# SequentialVoltageGenerator.net
KiCad netlist of a schematic drawn in EAGLE
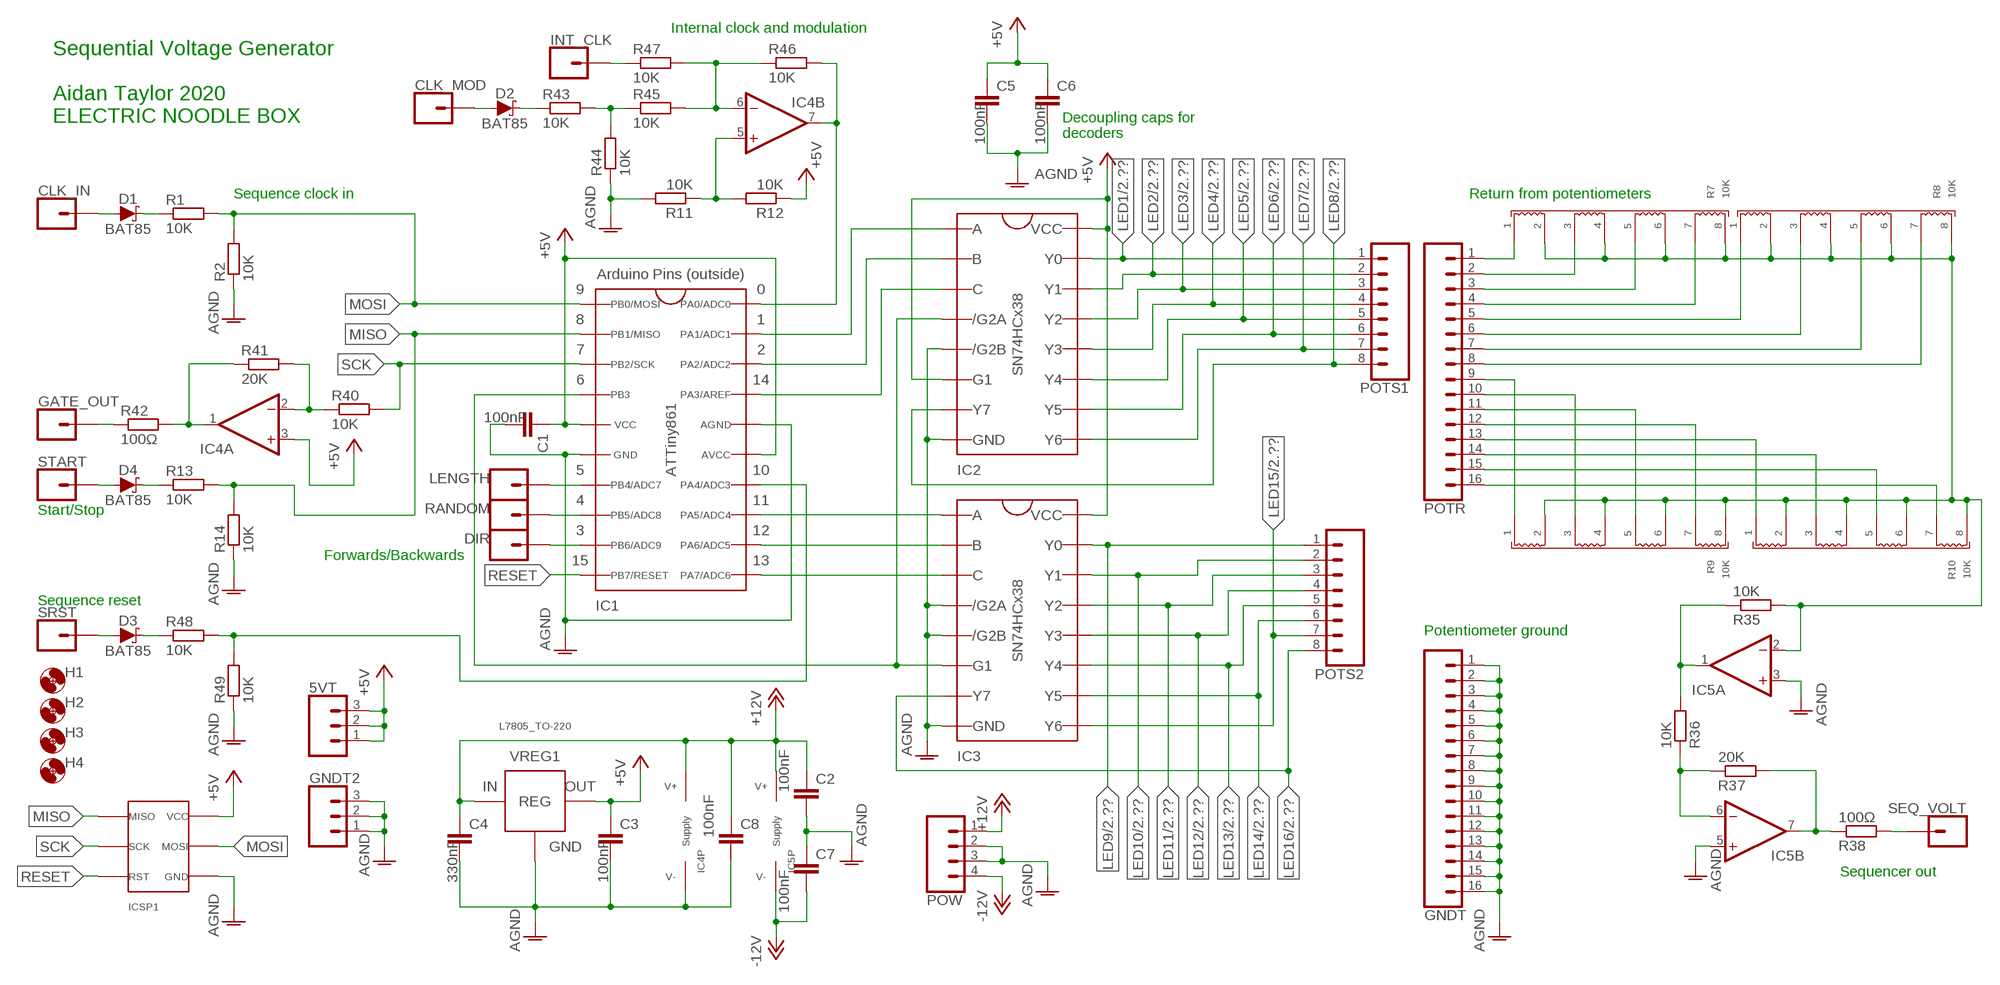
[diagram p0: schematic, sheet 1]
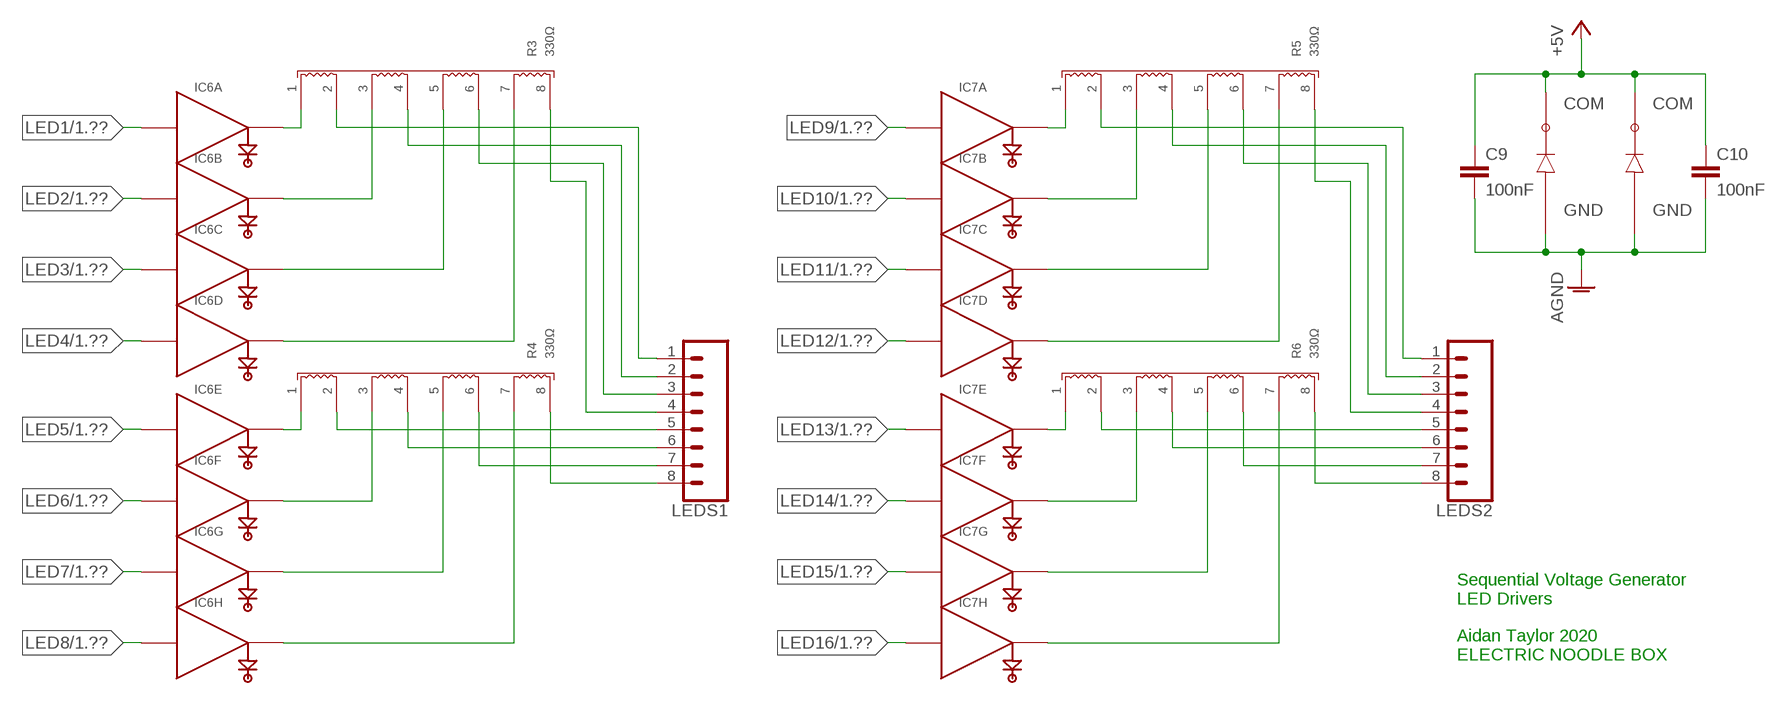
[diagram p1: schematic, sheet 2]

(export (version "E")
  (design (tool "Eeschema 10.0.6"))
  (components
    (comp (ref "C9")
      (value "100nF")
      (footprint "eagle-import:C050-025X075")
      (libsource (lib "eagle-import") (part "C-EU050-025X075"))
    )
    (comp (ref "C10")
      (value "100nF")
      (footprint "eagle-import:C050-025X075")
      (libsource (lib "eagle-import") (part "C-EU050-025X075"))
    )
    (comp (ref "IC6")
      (value "ULN2801_DIP")
      (footprint "eagle-import:DIL18")
      (libsource (lib "eagle-import") (part "ULN2801_DIP"))
    )
    (comp (ref "IC7")
      (value "ULN2801_DIP")
      (footprint "eagle-import:DIL18")
      (libsource (lib "eagle-import") (part "ULN2801_DIP"))
    )
    (comp (ref "LEDS1")
      (value "8XWIREPAD")
      (footprint "eagle-import:1X08")
      (libsource (lib "eagle-import") (part "8XWIREPAD"))
    )
    (comp (ref "LEDS2")
      (value "8XWIREPAD")
      (footprint "eagle-import:1X08")
      (libsource (lib "eagle-import") (part "8XWIREPAD"))
    )
    (comp (ref "R3")
      (value "330Ω")
      (footprint "eagle-import:4_ISO_RES_NET_2.54")
      (libsource (lib "eagle-import") (part "4XISO_RESISTOR_NETWORK_2.54"))
    )
    (comp (ref "R4")
      (value "330Ω")
      (footprint "eagle-import:4_ISO_RES_NET_2.54")
      (libsource (lib "eagle-import") (part "4XISO_RESISTOR_NETWORK_2.54"))
    )
    (comp (ref "R5")
      (value "330Ω")
      (footprint "eagle-import:4_ISO_RES_NET_2.54")
      (libsource (lib "eagle-import") (part "4XISO_RESISTOR_NETWORK_2.54"))
    )
    (comp (ref "R6")
      (value "330Ω")
      (footprint "eagle-import:4_ISO_RES_NET_2.54")
      (libsource (lib "eagle-import") (part "4XISO_RESISTOR_NETWORK_2.54"))
    )
    (comp (ref "5VT")
      (value "3XWIREPAD")
      (footprint "eagle-import:1X03")
      (libsource (lib "eagle-import") (part "3XWIREPAD"))
    )
    (comp (ref "C1")
      (value "100nF")
      (footprint "eagle-import:C050-025X075")
      (libsource (lib "eagle-import") (part "C-EU050-025X075"))
    )
    (comp (ref "C2")
      (value "100nF")
      (footprint "eagle-import:C050-025X075")
      (libsource (lib "eagle-import") (part "C-EU050-025X075"))
    )
    (comp (ref "C3")
      (value "100nF")
      (footprint "eagle-import:C050-025X075")
      (libsource (lib "eagle-import") (part "C-EU050-025X075"))
    )
    (comp (ref "C4")
      (value "330nF")
      (footprint "eagle-import:C050-025X075")
      (libsource (lib "eagle-import") (part "C-EU050-025X075"))
    )
    (comp (ref "C5")
      (value "100nF")
      (footprint "eagle-import:C050-025X075")
      (libsource (lib "eagle-import") (part "C-EU050-025X075"))
    )
    (comp (ref "C6")
      (value "100nF")
      (footprint "eagle-import:C050-025X075")
      (libsource (lib "eagle-import") (part "C-EU050-025X075"))
    )
    (comp (ref "C7")
      (value "100nF")
      (footprint "eagle-import:C050-025X075")
      (libsource (lib "eagle-import") (part "C-EU050-025X075"))
    )
    (comp (ref "C8")
      (value "100nF")
      (footprint "eagle-import:C050-025X075")
      (libsource (lib "eagle-import") (part "C-EU050-025X075"))
    )
    (comp (ref "CLK_IN")
      (value "1XWIREPAD")
      (footprint "eagle-import:1X01")
      (libsource (lib "eagle-import") (part "1XWIREPAD"))
    )
    (comp (ref "CLK_MOD")
      (value "1XWIREPAD")
      (footprint "eagle-import:1X01")
      (libsource (lib "eagle-import") (part "1XWIREPAD"))
    )
    (comp (ref "D1")
      (value "BAT85")
      (footprint "eagle-import:DO35-7")
      (libsource (lib "eagle-import") (part "SCHOTTKY_DO35"))
    )
    (comp (ref "D2")
      (value "BAT85")
      (footprint "eagle-import:DO35-7")
      (libsource (lib "eagle-import") (part "SCHOTTKY_DO35"))
    )
    (comp (ref "D3")
      (value "BAT85")
      (footprint "eagle-import:DO35-7")
      (libsource (lib "eagle-import") (part "SCHOTTKY_DO35"))
    )
    (comp (ref "D4")
      (value "BAT85")
      (footprint "eagle-import:DO35-7")
      (libsource (lib "eagle-import") (part "SCHOTTKY_DO35"))
    )
    (comp (ref "DIR")
      (value "1XWIREPAD")
      (footprint "eagle-import:1X01")
      (libsource (lib "eagle-import") (part "1XWIREPAD"))
    )
    (comp (ref "GATE_OUT")
      (value "1XWIREPAD")
      (footprint "eagle-import:1X01")
      (libsource (lib "eagle-import") (part "1XWIREPAD"))
    )
    (comp (ref "GNDT")
      (value "16XWIREPAD")
      (footprint "eagle-import:1X16")
      (libsource (lib "eagle-import") (part "16XWIREPAD"))
    )
    (comp (ref "GNDT2")
      (value "3XWIREPAD")
      (footprint "eagle-import:1X03")
      (libsource (lib "eagle-import") (part "3XWIREPAD"))
    )
    (comp (ref "H1")
      (value "MOUNT-HOLE3.2")
      (footprint "eagle-import:3,2")
      (libsource (lib "eagle-import") (part "MOUNT-HOLE3.2"))
    )
    (comp (ref "H2")
      (value "MOUNT-HOLE3.2")
      (footprint "eagle-import:3,2")
      (libsource (lib "eagle-import") (part "MOUNT-HOLE3.2"))
    )
    (comp (ref "H3")
      (value "MOUNT-HOLE3.2")
      (footprint "eagle-import:3,2")
      (libsource (lib "eagle-import") (part "MOUNT-HOLE3.2"))
    )
    (comp (ref "H4")
      (value "MOUNT-HOLE3.2")
      (footprint "eagle-import:3,2")
      (libsource (lib "eagle-import") (part "MOUNT-HOLE3.2"))
    )
    (comp (ref "IC1")
      (value "ATTINY861_DIP")
      (footprint "eagle-import:DIL20")
      (libsource (lib "eagle-import") (part "ATTINY861_DIP"))
    )
    (comp (ref "IC2")
      (value "SN74HCX38")
      (footprint "eagle-import:DIL16")
      (libsource (lib "eagle-import") (part "SN74HCX38"))
    )
    (comp (ref "IC3")
      (value "SN74HCX38")
      (footprint "eagle-import:DIL16")
      (libsource (lib "eagle-import") (part "SN74HCX38"))
    )
    (comp (ref "IC4")
      (value "LM358_DIP")
      (footprint "eagle-import:DIL08")
      (libsource (lib "eagle-import") (part "LM358_DIP"))
    )
    (comp (ref "IC5")
      (value "TL0X2_DIP")
      (footprint "eagle-import:DIL08")
      (libsource (lib "eagle-import") (part "TL0X2_DIP"))
    )
    (comp (ref "ICSP1")
      (value "ICSP_2.54")
      (footprint "eagle-import:2X3")
      (libsource (lib "eagle-import") (part "ICSP_2.54"))
    )
    (comp (ref "INT_CLK")
      (value "1XWIREPAD")
      (footprint "eagle-import:1X01")
      (libsource (lib "eagle-import") (part "1XWIREPAD"))
    )
    (comp (ref "LENGTH")
      (value "1XWIREPAD")
      (footprint "eagle-import:1X01")
      (libsource (lib "eagle-import") (part "1XWIREPAD"))
    )
    (comp (ref "POTR")
      (value "16XWIREPAD")
      (footprint "eagle-import:1X16")
      (libsource (lib "eagle-import") (part "16XWIREPAD"))
    )
    (comp (ref "POTS1")
      (value "8XWIREPAD")
      (footprint "eagle-import:1X08")
      (libsource (lib "eagle-import") (part "8XWIREPAD"))
    )
    (comp (ref "POTS2")
      (value "8XWIREPAD")
      (footprint "eagle-import:1X08")
      (libsource (lib "eagle-import") (part "8XWIREPAD"))
    )
    (comp (ref "POW")
      (value "4XMOLEX")
      (footprint "eagle-import:MOLEX-1X4")
      (libsource (lib "eagle-import") (part "4XMOLEX"))
    )
    (comp (ref "R1")
      (value "10K")
      (footprint "eagle-import:0207_10")
      (libsource (lib "eagle-import") (part "R-EU_0207/10"))
    )
    (comp (ref "R2")
      (value "10K")
      (footprint "eagle-import:0207_10")
      (libsource (lib "eagle-import") (part "R-EU_0207/10"))
    )
    (comp (ref "R7")
      (value "10K")
      (footprint "eagle-import:4_ISO_RES_NET_2.54")
      (libsource (lib "eagle-import") (part "4XISO_RESISTOR_NETWORK_2.54"))
    )
    (comp (ref "R8")
      (value "10K")
      (footprint "eagle-import:4_ISO_RES_NET_2.54")
      (libsource (lib "eagle-import") (part "4XISO_RESISTOR_NETWORK_2.54"))
    )
    (comp (ref "R9")
      (value "10K")
      (footprint "eagle-import:4_ISO_RES_NET_2.54")
      (libsource (lib "eagle-import") (part "4XISO_RESISTOR_NETWORK_2.54"))
    )
    (comp (ref "R10")
      (value "10K")
      (footprint "eagle-import:4_ISO_RES_NET_2.54")
      (libsource (lib "eagle-import") (part "4XISO_RESISTOR_NETWORK_2.54"))
    )
    (comp (ref "R11")
      (value "10K")
      (footprint "eagle-import:0207_10")
      (libsource (lib "eagle-import") (part "R-EU_0207/10"))
    )
    (comp (ref "R12")
      (value "10K")
      (footprint "eagle-import:0207_10")
      (libsource (lib "eagle-import") (part "R-EU_0207/10"))
    )
    (comp (ref "R13")
      (value "10K")
      (footprint "eagle-import:0207_10")
      (libsource (lib "eagle-import") (part "R-EU_0207/10"))
    )
    (comp (ref "R14")
      (value "10K")
      (footprint "eagle-import:0207_10")
      (libsource (lib "eagle-import") (part "R-EU_0207/10"))
    )
    (comp (ref "R35")
      (value "10K")
      (footprint "eagle-import:0207_10")
      (libsource (lib "eagle-import") (part "R-EU_0207/10"))
    )
    (comp (ref "R36")
      (value "10K")
      (footprint "eagle-import:0207_10")
      (libsource (lib "eagle-import") (part "R-EU_0207/10"))
    )
    (comp (ref "R37")
      (value "20K")
      (footprint "eagle-import:0207_10")
      (libsource (lib "eagle-import") (part "R-EU_0207/10"))
    )
    (comp (ref "R38")
      (value "100Ω")
      (footprint "eagle-import:0207_10")
      (libsource (lib "eagle-import") (part "R-EU_0207/10"))
    )
    (comp (ref "R40")
      (value "10K")
      (footprint "eagle-import:0207_10")
      (libsource (lib "eagle-import") (part "R-EU_0207/10"))
    )
    (comp (ref "R41")
      (value "20K")
      (footprint "eagle-import:0207_10")
      (libsource (lib "eagle-import") (part "R-EU_0207/10"))
    )
    (comp (ref "R42")
      (value "100Ω")
      (footprint "eagle-import:0207_10")
      (libsource (lib "eagle-import") (part "R-EU_0207/10"))
    )
    (comp (ref "R43")
      (value "10K")
      (footprint "eagle-import:0207_10")
      (libsource (lib "eagle-import") (part "R-EU_0207/10"))
    )
    (comp (ref "R44")
      (value "10K")
      (footprint "eagle-import:0207_10")
      (libsource (lib "eagle-import") (part "R-EU_0207/10"))
    )
    (comp (ref "R45")
      (value "10K")
      (footprint "eagle-import:0207_10")
      (libsource (lib "eagle-import") (part "R-EU_0207/10"))
    )
    (comp (ref "R46")
      (value "10K")
      (footprint "eagle-import:0207_10")
      (libsource (lib "eagle-import") (part "R-EU_0207/10"))
    )
    (comp (ref "R47")
      (value "10K")
      (footprint "eagle-import:0207_10")
      (libsource (lib "eagle-import") (part "R-EU_0207/10"))
    )
    (comp (ref "R48")
      (value "10K")
      (footprint "eagle-import:0207_10")
      (libsource (lib "eagle-import") (part "R-EU_0207/10"))
    )
    (comp (ref "R49")
      (value "10K")
      (footprint "eagle-import:0207_10")
      (libsource (lib "eagle-import") (part "R-EU_0207/10"))
    )
    (comp (ref "RANDOM")
      (value "1XWIREPAD")
      (footprint "eagle-import:1X01")
      (libsource (lib "eagle-import") (part "1XWIREPAD"))
    )
    (comp (ref "SEQ_VOLT")
      (value "1XWIREPAD")
      (footprint "eagle-import:1X01")
      (libsource (lib "eagle-import") (part "1XWIREPAD"))
    )
    (comp (ref "SRST")
      (value "1XWIREPAD")
      (footprint "eagle-import:1X01")
      (libsource (lib "eagle-import") (part "1XWIREPAD"))
    )
    (comp (ref "START")
      (value "1XWIREPAD")
      (footprint "eagle-import:1X01")
      (libsource (lib "eagle-import") (part "1XWIREPAD"))
    )
    (comp (ref "VREG1")
      (value "L7805_TO-220")
      (footprint "eagle-import:TO220H")
      (libsource (lib "eagle-import") (part "L7805_TO-220"))
    )
  )
  (nets
    (net (code "1") (name "+5V") (class "Default")
      (node (ref "5VT") (pin "1") (pinfunction "1_1") (pintype "passive"))
      (node (ref "5VT") (pin "2") (pinfunction "2_2") (pintype "passive"))
      (node (ref "5VT") (pin "3") (pinfunction "3_3") (pintype "passive"))
      (node (ref "C1") (pin "1") (pinfunction "1_1") (pintype "passive"))
      (node (ref "C10") (pin "1") (pinfunction "1_1") (pintype "passive"))
      (node (ref "C3") (pin "1") (pinfunction "1_1") (pintype "passive"))
      (node (ref "C5") (pin "1") (pinfunction "1_1") (pintype "passive"))
      (node (ref "C6") (pin "1") (pinfunction "1_1") (pintype "passive"))
      (node (ref "C9") (pin "1") (pinfunction "1_1") (pintype "passive"))
      (node (ref "IC1") (pin "15") (pinfunction "AVCC_15") (pintype "bidirectional"))
      (node (ref "IC1") (pin "5") (pinfunction "VCC_5") (pintype "power_in"))
      (node (ref "IC2") (pin "16") (pinfunction "16_VCC_16") (pintype "power_in"))
      (node (ref "IC2") (pin "6") (pinfunction "6_G1_6") (pintype "input"))
      (node (ref "IC3") (pin "16") (pinfunction "16_VCC_16") (pintype "power_in"))
      (node (ref "IC4") (pin "3") (pinfunction "+IN_3") (pintype "input"))
      (node (ref "IC6") (pin "10") (pinfunction "COM_10") (pintype "power_in"))
      (node (ref "IC7") (pin "10") (pinfunction "COM_10") (pintype "power_in"))
      (node (ref "ICSP1") (pin "2") (pinfunction "6VCC_2") (pintype "power_in"))
      (node (ref "R12") (pin "1") (pinfunction "1_1") (pintype "passive"))
      (node (ref "VREG1") (pin "3") (pinfunction "VOUT_3") (pintype "output"))
    )
    (net (code "2") (name "+12V") (class "Default")
      (node (ref "C2") (pin "1") (pinfunction "1_1") (pintype "passive"))
      (node (ref "C4") (pin "1") (pinfunction "1_1") (pintype "passive"))
      (node (ref "C8") (pin "1") (pinfunction "1_1") (pintype "passive"))
      (node (ref "IC4") (pin "8") (pinfunction "V+_8") (pintype "bidirectional"))
      (node (ref "IC5") (pin "8") (pinfunction "V+_8") (pintype "bidirectional"))
      (node (ref "POW") (pin "1") (pinfunction "1_1") (pintype "passive"))
      (node (ref "VREG1") (pin "1") (pinfunction "VIN_1") (pintype "input"))
    )
    (net (code "3") (name "-12V") (class "Default")
      (node (ref "C7") (pin "2") (pinfunction "2_2") (pintype "passive"))
      (node (ref "IC5") (pin "4") (pinfunction "V-_4") (pintype "bidirectional"))
      (node (ref "POW") (pin "4") (pinfunction "4_4") (pintype "passive"))
    )
    (net (code "4") (name "AGND") (class "Default")
      (node (ref "C1") (pin "2") (pinfunction "2_2") (pintype "passive"))
      (node (ref "C10") (pin "2") (pinfunction "2_2") (pintype "passive"))
      (node (ref "C2") (pin "2") (pinfunction "2_2") (pintype "passive"))
      (node (ref "C3") (pin "2") (pinfunction "2_2") (pintype "passive"))
      (node (ref "C4") (pin "2") (pinfunction "2_2") (pintype "passive"))
      (node (ref "C5") (pin "2") (pinfunction "2_2") (pintype "passive"))
      (node (ref "C6") (pin "2") (pinfunction "2_2") (pintype "passive"))
      (node (ref "C7") (pin "1") (pinfunction "1_1") (pintype "passive"))
      (node (ref "C8") (pin "2") (pinfunction "2_2") (pintype "passive"))
      (node (ref "C9") (pin "2") (pinfunction "2_2") (pintype "passive"))
      (node (ref "GNDT") (pin "1") (pinfunction "1_1") (pintype "passive"))
      (node (ref "GNDT") (pin "10") (pinfunction "10_10") (pintype "passive"))
      (node (ref "GNDT") (pin "11") (pinfunction "11_11") (pintype "passive"))
      (node (ref "GNDT") (pin "12") (pinfunction "12_12") (pintype "passive"))
      (node (ref "GNDT") (pin "13") (pinfunction "13_13") (pintype "passive"))
      (node (ref "GNDT") (pin "14") (pinfunction "14_14") (pintype "passive"))
      (node (ref "GNDT") (pin "15") (pinfunction "15_15") (pintype "passive"))
      (node (ref "GNDT") (pin "16") (pinfunction "16_16") (pintype "passive"))
      (node (ref "GNDT") (pin "2") (pinfunction "2_2") (pintype "passive"))
      (node (ref "GNDT") (pin "3") (pinfunction "3_3") (pintype "passive"))
      (node (ref "GNDT") (pin "4") (pinfunction "4_4") (pintype "passive"))
      (node (ref "GNDT") (pin "5") (pinfunction "5_5") (pintype "passive"))
      (node (ref "GNDT") (pin "6") (pinfunction "6_6") (pintype "passive"))
      (node (ref "GNDT") (pin "7") (pinfunction "7_7") (pintype "passive"))
      (node (ref "GNDT") (pin "8") (pinfunction "8_8") (pintype "passive"))
      (node (ref "GNDT") (pin "9") (pinfunction "9_9") (pintype "passive"))
      (node (ref "GNDT2") (pin "1") (pinfunction "1_1") (pintype "passive"))
      (node (ref "GNDT2") (pin "2") (pinfunction "2_2") (pintype "passive"))
      (node (ref "GNDT2") (pin "3") (pinfunction "3_3") (pintype "passive"))
      (node (ref "IC1") (pin "16") (pinfunction "AGND_16") (pintype "bidirectional"))
      (node (ref "IC1") (pin "6") (pinfunction "GND_6") (pintype "power_in"))
      (node (ref "IC2") (pin "5") (pinfunction "5_/G2B_5") (pintype "input"))
      (node (ref "IC2") (pin "8") (pinfunction "8_GND_8") (pintype "power_in"))
      (node (ref "IC3") (pin "4") (pinfunction "4_/G2A_4") (pintype "input"))
      (node (ref "IC3") (pin "5") (pinfunction "5_/G2B_5") (pintype "input"))
      (node (ref "IC3") (pin "8") (pinfunction "8_GND_8") (pintype "power_in"))
      (node (ref "IC4") (pin "4") (pinfunction "V-_4") (pintype "bidirectional"))
      (node (ref "IC5") (pin "3") (pinfunction "+IN_3") (pintype "input"))
      (node (ref "IC5") (pin "5") (pinfunction "+IN_5") (pintype "input"))
      (node (ref "IC6") (pin "9") (pinfunction "GND_9") (pintype "power_in"))
      (node (ref "IC7") (pin "9") (pinfunction "GND_9") (pintype "power_in"))
      (node (ref "ICSP1") (pin "6") (pinfunction "4GND_6") (pintype "power_in"))
      (node (ref "POW") (pin "2") (pinfunction "2_2") (pintype "passive"))
      (node (ref "POW") (pin "3") (pinfunction "3_3") (pintype "passive"))
      (node (ref "R11") (pin "2") (pinfunction "2_2") (pintype "passive"))
      (node (ref "R14") (pin "1") (pinfunction "1_1") (pintype "passive"))
      (node (ref "R2") (pin "1") (pinfunction "1_1") (pintype "passive"))
      (node (ref "R44") (pin "1") (pinfunction "1_1") (pintype "passive"))
      (node (ref "R49") (pin "1") (pinfunction "1_1") (pintype "passive"))
      (node (ref "VREG1") (pin "2") (pinfunction "GND_2") (pintype "power_in"))
    )
    (net (code "5") (name "LED1") (class "Default")
      (node (ref "IC2") (pin "15") (pinfunction "15_Y0_15") (pintype "output"))
      (node (ref "IC6") (pin "1") (pinfunction "IN_1") (pintype "input"))
      (node (ref "POTS1") (pin "1") (pinfunction "1_1") (pintype "passive"))
    )
    (net (code "6") (name "LED2") (class "Default")
      (node (ref "IC2") (pin "14") (pinfunction "14_Y1_14") (pintype "output"))
      (node (ref "IC6") (pin "2") (pinfunction "IN_2") (pintype "input"))
      (node (ref "POTS1") (pin "2") (pinfunction "2_2") (pintype "passive"))
    )
    (net (code "7") (name "LED3") (class "Default")
      (node (ref "IC2") (pin "13") (pinfunction "13_Y2_13") (pintype "output"))
      (node (ref "IC6") (pin "3") (pinfunction "IN_3") (pintype "input"))
      (node (ref "POTS1") (pin "3") (pinfunction "3_3") (pintype "passive"))
    )
    (net (code "8") (name "LED4") (class "Default")
      (node (ref "IC2") (pin "12") (pinfunction "12_Y3_12") (pintype "output"))
      (node (ref "IC6") (pin "4") (pinfunction "IN_4") (pintype "input"))
      (node (ref "POTS1") (pin "4") (pinfunction "4_4") (pintype "passive"))
    )
    (net (code "9") (name "LED5") (class "Default")
      (node (ref "IC2") (pin "11") (pinfunction "11_Y4_11") (pintype "output"))
      (node (ref "IC6") (pin "5") (pinfunction "IN_5") (pintype "input"))
      (node (ref "POTS1") (pin "5") (pinfunction "5_5") (pintype "passive"))
    )
    (net (code "10") (name "LED6") (class "Default")
      (node (ref "IC2") (pin "10") (pinfunction "10_Y5_10") (pintype "output"))
      (node (ref "IC6") (pin "6") (pinfunction "IN_6") (pintype "input"))
      (node (ref "POTS1") (pin "6") (pinfunction "6_6") (pintype "passive"))
    )
    (net (code "11") (name "LED7") (class "Default")
      (node (ref "IC2") (pin "9") (pinfunction "9_Y6_9") (pintype "output"))
      (node (ref "IC6") (pin "7") (pinfunction "IN_7") (pintype "input"))
      (node (ref "POTS1") (pin "7") (pinfunction "7_7") (pintype "passive"))
    )
    (net (code "12") (name "LED8") (class "Default")
      (node (ref "IC2") (pin "7") (pinfunction "7_Y7_7") (pintype "output"))
      (node (ref "IC6") (pin "8") (pinfunction "IN_8") (pintype "input"))
      (node (ref "POTS1") (pin "8") (pinfunction "8_8") (pintype "passive"))
    )
    (net (code "13") (name "LED9") (class "Default")
      (node (ref "IC3") (pin "15") (pinfunction "15_Y0_15") (pintype "output"))
      (node (ref "IC7") (pin "1") (pinfunction "IN_1") (pintype "input"))
      (node (ref "POTS2") (pin "1") (pinfunction "1_1") (pintype "passive"))
    )
    (net (code "14") (name "LED10") (class "Default")
      (node (ref "IC3") (pin "14") (pinfunction "14_Y1_14") (pintype "output"))
      (node (ref "IC7") (pin "2") (pinfunction "IN_2") (pintype "input"))
      (node (ref "POTS2") (pin "2") (pinfunction "2_2") (pintype "passive"))
    )
    (net (code "15") (name "LED11") (class "Default")
      (node (ref "IC3") (pin "13") (pinfunction "13_Y2_13") (pintype "output"))
      (node (ref "IC7") (pin "3") (pinfunction "IN_3") (pintype "input"))
      (node (ref "POTS2") (pin "3") (pinfunction "3_3") (pintype "passive"))
    )
    (net (code "16") (name "LED12") (class "Default")
      (node (ref "IC3") (pin "12") (pinfunction "12_Y3_12") (pintype "output"))
      (node (ref "IC7") (pin "4") (pinfunction "IN_4") (pintype "input"))
      (node (ref "POTS2") (pin "4") (pinfunction "4_4") (pintype "passive"))
    )
    (net (code "17") (name "LED13") (class "Default")
      (node (ref "IC3") (pin "11") (pinfunction "11_Y4_11") (pintype "output"))
      (node (ref "IC7") (pin "5") (pinfunction "IN_5") (pintype "input"))
      (node (ref "POTS2") (pin "5") (pinfunction "5_5") (pintype "passive"))
    )
    (net (code "18") (name "LED14") (class "Default")
      (node (ref "IC3") (pin "10") (pinfunction "10_Y5_10") (pintype "output"))
      (node (ref "IC7") (pin "6") (pinfunction "IN_6") (pintype "input"))
      (node (ref "POTS2") (pin "6") (pinfunction "6_6") (pintype "passive"))
    )
    (net (code "19") (name "LED15") (class "Default")
      (node (ref "IC3") (pin "9") (pinfunction "9_Y6_9") (pintype "output"))
      (node (ref "IC7") (pin "7") (pinfunction "IN_7") (pintype "input"))
      (node (ref "POTS2") (pin "7") (pinfunction "7_7") (pintype "passive"))
    )
    (net (code "20") (name "LED16") (class "Default")
      (node (ref "IC3") (pin "7") (pinfunction "7_Y7_7") (pintype "output"))
      (node (ref "IC7") (pin "8") (pinfunction "IN_8") (pintype "input"))
      (node (ref "POTS2") (pin "8") (pinfunction "8_8") (pintype "passive"))
    )
    (net (code "21") (name "MISO") (class "Default")
      (node (ref "IC1") (pin "2") (pinfunction "2_PB1_2") (pintype "bidirectional"))
      (node (ref "ICSP1") (pin "1") (pinfunction "1MISO_1") (pintype "bidirectional"))
      (node (ref "R13") (pin "2") (pinfunction "2_2") (pintype "passive"))
      (node (ref "R14") (pin "2") (pinfunction "2_2") (pintype "passive"))
    )
    (net (code "22") (name "MOSI") (class "Default")
      (node (ref "IC1") (pin "1") (pinfunction "1_PB0_1") (pintype "bidirectional"))
      (node (ref "ICSP1") (pin "4") (pinfunction "5MOSI_4") (pintype "bidirectional"))
      (node (ref "R1") (pin "2") (pinfunction "2_2") (pintype "passive"))
      (node (ref "R2") (pin "2") (pinfunction "2_2") (pintype "passive"))
    )
    (net (code "23") (name "Net-(CLK_IN-Pad1)") (class "Default")
      (node (ref "CLK_IN") (pin "1") (pinfunction "1_1") (pintype "passive"))
      (node (ref "D1") (pin "A") (pinfunction "A_A") (pintype "passive"))
    )
    (net (code "24") (name "Net-(CLK_MOD-Pad1)") (class "Default")
      (node (ref "CLK_MOD") (pin "1") (pinfunction "1_1") (pintype "passive"))
      (node (ref "D2") (pin "A") (pinfunction "A_A") (pintype "passive"))
    )
    (net (code "25") (name "Net-(D1-PadC)") (class "Default")
      (node (ref "D1") (pin "C") (pinfunction "C_C") (pintype "passive"))
      (node (ref "R1") (pin "1") (pinfunction "1_1") (pintype "passive"))
    )
    (net (code "26") (name "Net-(D2-PadC)") (class "Default")
      (node (ref "D2") (pin "C") (pinfunction "C_C") (pintype "passive"))
      (node (ref "R43") (pin "1") (pinfunction "1_1") (pintype "passive"))
    )
    (net (code "27") (name "Net-(D3-PadA)") (class "Default")
      (node (ref "D3") (pin "A") (pinfunction "A_A") (pintype "passive"))
      (node (ref "SRST") (pin "1") (pinfunction "1_1") (pintype "passive"))
    )
    (net (code "28") (name "Net-(D3-PadC)") (class "Default")
      (node (ref "D3") (pin "C") (pinfunction "C_C") (pintype "passive"))
      (node (ref "R48") (pin "1") (pinfunction "1_1") (pintype "passive"))
    )
    (net (code "29") (name "Net-(D4-PadA)") (class "Default")
      (node (ref "D4") (pin "A") (pinfunction "A_A") (pintype "passive"))
      (node (ref "START") (pin "1") (pinfunction "1_1") (pintype "passive"))
    )
    (net (code "30") (name "Net-(D4-PadC)") (class "Default")
      (node (ref "D4") (pin "C") (pinfunction "C_C") (pintype "passive"))
      (node (ref "R13") (pin "1") (pinfunction "1_1") (pintype "passive"))
    )
    (net (code "31") (name "Net-(GATE_OUT-Pad1)") (class "Default")
      (node (ref "GATE_OUT") (pin "1") (pinfunction "1_1") (pintype "passive"))
      (node (ref "R42") (pin "1") (pinfunction "1_1") (pintype "passive"))
    )
    (net (code "32") (name "Net-(IC1-4_PB3)") (class "Default")
      (node (ref "IC1") (pin "4") (pinfunction "4_PB3_4") (pintype "bidirectional"))
      (node (ref "IC2") (pin "4") (pinfunction "4_/G2A_4") (pintype "input"))
      (node (ref "IC3") (pin "6") (pinfunction "6_G1_6") (pintype "input"))
    )
    (net (code "33") (name "Net-(IC1-7_PB4)") (class "Default")
      (node (ref "IC1") (pin "7") (pinfunction "7_PB4_7") (pintype "bidirectional"))
      (node (ref "LENGTH") (pin "1") (pinfunction "1_1") (pintype "passive"))
    )
    (net (code "34") (name "Net-(IC1-8_PB5)") (class "Default")
      (node (ref "IC1") (pin "8") (pinfunction "8_PB5_8") (pintype "bidirectional"))
      (node (ref "RANDOM") (pin "1") (pinfunction "1_1") (pintype "passive"))
    )
    (net (code "35") (name "Net-(IC1-9_PB6)") (class "Default")
      (node (ref "DIR") (pin "1") (pinfunction "1_1") (pintype "passive"))
      (node (ref "IC1") (pin "9") (pinfunction "9_PB6_9") (pintype "bidirectional"))
    )
    (net (code "36") (name "Net-(IC1-11_PA7)") (class "Default")
      (node (ref "IC1") (pin "11") (pinfunction "11_PA7_11") (pintype "bidirectional"))
      (node (ref "IC3") (pin "3") (pinfunction "3_C_3") (pintype "input"))
    )
    (net (code "37") (name "Net-(IC1-12_PA6)") (class "Default")
      (node (ref "IC1") (pin "12") (pinfunction "12_PA6_12") (pintype "bidirectional"))
      (node (ref "IC3") (pin "2") (pinfunction "2_B_2") (pintype "input"))
    )
    (net (code "38") (name "Net-(IC1-13_PA5)") (class "Default")
      (node (ref "IC1") (pin "13") (pinfunction "13_PA5_13") (pintype "bidirectional"))
      (node (ref "IC3") (pin "1") (pinfunction "1_A_1") (pintype "input"))
    )
    (net (code "39") (name "Net-(IC1-14_PA4)") (class "Default")
      (node (ref "IC1") (pin "14") (pinfunction "14_PA4_14") (pintype "bidirectional"))
      (node (ref "R48") (pin "2") (pinfunction "2_2") (pintype "passive"))
      (node (ref "R49") (pin "2") (pinfunction "2_2") (pintype "passive"))
    )
    (net (code "40") (name "Net-(IC1-17_PA3)") (class "Default")
      (node (ref "IC1") (pin "17") (pinfunction "17_PA3_17") (pintype "bidirectional"))
      (node (ref "IC2") (pin "3") (pinfunction "3_C_3") (pintype "input"))
    )
    (net (code "41") (name "Net-(IC1-18_PA2)") (class "Default")
      (node (ref "IC1") (pin "18") (pinfunction "18_PA2_18") (pintype "bidirectional"))
      (node (ref "IC2") (pin "2") (pinfunction "2_B_2") (pintype "input"))
    )
    (net (code "42") (name "Net-(IC1-19_PA1)") (class "Default")
      (node (ref "IC1") (pin "19") (pinfunction "19_PA1_19") (pintype "bidirectional"))
      (node (ref "IC2") (pin "1") (pinfunction "1_A_1") (pintype "input"))
    )
    (net (code "43") (name "Net-(IC1-20_PA0)") (class "Default")
      (node (ref "IC1") (pin "20") (pinfunction "20_PA0_20") (pintype "bidirectional"))
      (node (ref "IC4") (pin "7") (pinfunction "OUT_7") (pintype "output"))
      (node (ref "R46") (pin "2") (pinfunction "2_2") (pintype "passive"))
    )
    (net (code "44") (name "Net-(IC4A--IN)") (class "Default")
      (node (ref "IC4") (pin "2") (pinfunction "-IN_2") (pintype "input"))
      (node (ref "R40") (pin "1") (pinfunction "1_1") (pintype "passive"))
      (node (ref "R41") (pin "2") (pinfunction "2_2") (pintype "passive"))
    )
    (net (code "45") (name "Net-(IC4A-OUT)") (class "Default")
      (node (ref "IC4") (pin "1") (pinfunction "OUT_1") (pintype "output"))
      (node (ref "R41") (pin "1") (pinfunction "1_1") (pintype "passive"))
      (node (ref "R42") (pin "2") (pinfunction "2_2") (pintype "passive"))
    )
    (net (code "46") (name "Net-(IC4B-+IN)") (class "Default")
      (node (ref "IC4") (pin "5") (pinfunction "+IN_5") (pintype "input"))
      (node (ref "R11") (pin "1") (pinfunction "1_1") (pintype "passive"))
      (node (ref "R12") (pin "2") (pinfunction "2_2") (pintype "passive"))
    )
    (net (code "47") (name "Net-(IC4B--IN)") (class "Default")
      (node (ref "IC4") (pin "6") (pinfunction "-IN_6") (pintype "input"))
      (node (ref "R45") (pin "2") (pinfunction "2_2") (pintype "passive"))
      (node (ref "R46") (pin "1") (pinfunction "1_1") (pintype "passive"))
      (node (ref "R47") (pin "2") (pinfunction "2_2") (pintype "passive"))
    )
    (net (code "48") (name "Net-(IC5A--IN)") (class "Default")
      (node (ref "IC5") (pin "2") (pinfunction "-IN_2") (pintype "input"))
      (node (ref "R10") (pin "P$2") (pinfunction "P$2_P$2") (pintype "bidirectional"))
      (node (ref "R10") (pin "P$4") (pinfunction "P$4_P$4") (pintype "bidirectional"))
      (node (ref "R10") (pin "P$6") (pinfunction "P$6_P$6") (pintype "bidirectional"))
      (node (ref "R10") (pin "P$8") (pinfunction "P$8_P$8") (pintype "bidirectional"))
      (node (ref "R35") (pin "2") (pinfunction "2_2") (pintype "passive"))
      (node (ref "R7") (pin "P$2") (pinfunction "P$2_P$2") (pintype "bidirectional"))
      (node (ref "R7") (pin "P$4") (pinfunction "P$4_P$4") (pintype "bidirectional"))
      (node (ref "R7") (pin "P$6") (pinfunction "P$6_P$6") (pintype "bidirectional"))
      (node (ref "R7") (pin "P$8") (pinfunction "P$8_P$8") (pintype "bidirectional"))
      (node (ref "R8") (pin "P$2") (pinfunction "P$2_P$2") (pintype "bidirectional"))
      (node (ref "R8") (pin "P$4") (pinfunction "P$4_P$4") (pintype "bidirectional"))
      (node (ref "R8") (pin "P$6") (pinfunction "P$6_P$6") (pintype "bidirectional"))
      (node (ref "R8") (pin "P$8") (pinfunction "P$8_P$8") (pintype "bidirectional"))
      (node (ref "R9") (pin "P$2") (pinfunction "P$2_P$2") (pintype "bidirectional"))
      (node (ref "R9") (pin "P$4") (pinfunction "P$4_P$4") (pintype "bidirectional"))
      (node (ref "R9") (pin "P$6") (pinfunction "P$6_P$6") (pintype "bidirectional"))
      (node (ref "R9") (pin "P$8") (pinfunction "P$8_P$8") (pintype "bidirectional"))
    )
    (net (code "49") (name "Net-(IC5A-OUT)") (class "Default")
      (node (ref "IC5") (pin "1") (pinfunction "OUT_1") (pintype "output"))
      (node (ref "R35") (pin "1") (pinfunction "1_1") (pintype "passive"))
      (node (ref "R36") (pin "2") (pinfunction "2_2") (pintype "passive"))
    )
    (net (code "50") (name "Net-(IC5B--IN)") (class "Default")
      (node (ref "IC5") (pin "6") (pinfunction "-IN_6") (pintype "input"))
      (node (ref "R36") (pin "1") (pinfunction "1_1") (pintype "passive"))
      (node (ref "R37") (pin "1") (pinfunction "1_1") (pintype "passive"))
    )
    (net (code "51") (name "Net-(IC5B-OUT)") (class "Default")
      (node (ref "IC5") (pin "7") (pinfunction "OUT_7") (pintype "output"))
      (node (ref "R37") (pin "2") (pinfunction "2_2") (pintype "passive"))
      (node (ref "R38") (pin "1") (pinfunction "1_1") (pintype "passive"))
    )
    (net (code "52") (name "Net-(IC6A-P$2)") (class "Default")
      (node (ref "IC6") (pin "18") (pinfunction "P$2_18") (pintype "output"))
      (node (ref "R3") (pin "P$1") (pinfunction "P$1_P$1") (pintype "bidirectional"))
    )
    (net (code "53") (name "Net-(IC6B-P$2)") (class "Default")
      (node (ref "IC6") (pin "17") (pinfunction "P$2_17") (pintype "output"))
      (node (ref "R3") (pin "P$3") (pinfunction "P$3_P$3") (pintype "bidirectional"))
    )
    (net (code "54") (name "Net-(IC6C-P$2)") (class "Default")
      (node (ref "IC6") (pin "16") (pinfunction "P$2_16") (pintype "output"))
      (node (ref "R3") (pin "P$5") (pinfunction "P$5_P$5") (pintype "bidirectional"))
    )
    (net (code "55") (name "Net-(IC6D-P$2)") (class "Default")
      (node (ref "IC6") (pin "15") (pinfunction "P$2_15") (pintype "output"))
      (node (ref "R3") (pin "P$7") (pinfunction "P$7_P$7") (pintype "bidirectional"))
    )
    (net (code "56") (name "Net-(IC6E-P$2)") (class "Default")
      (node (ref "IC6") (pin "14") (pinfunction "P$2_14") (pintype "output"))
      (node (ref "R4") (pin "P$1") (pinfunction "P$1_P$1") (pintype "bidirectional"))
    )
    (net (code "57") (name "Net-(IC6F-P$2)") (class "Default")
      (node (ref "IC6") (pin "13") (pinfunction "P$2_13") (pintype "output"))
      (node (ref "R4") (pin "P$3") (pinfunction "P$3_P$3") (pintype "bidirectional"))
    )
    (net (code "58") (name "Net-(IC6G-P$2)") (class "Default")
      (node (ref "IC6") (pin "12") (pinfunction "P$2_12") (pintype "output"))
      (node (ref "R4") (pin "P$5") (pinfunction "P$5_P$5") (pintype "bidirectional"))
    )
    (net (code "59") (name "Net-(IC6I-P$2)") (class "Default")
      (node (ref "IC6") (pin "11") (pinfunction "P$2_11") (pintype "output"))
      (node (ref "R4") (pin "P$7") (pinfunction "P$7_P$7") (pintype "bidirectional"))
    )
    (net (code "60") (name "Net-(IC7A-P$2)") (class "Default")
      (node (ref "IC7") (pin "18") (pinfunction "P$2_18") (pintype "output"))
      (node (ref "R5") (pin "P$1") (pinfunction "P$1_P$1") (pintype "bidirectional"))
    )
    (net (code "61") (name "Net-(IC7B-P$2)") (class "Default")
      (node (ref "IC7") (pin "17") (pinfunction "P$2_17") (pintype "output"))
      (node (ref "R5") (pin "P$3") (pinfunction "P$3_P$3") (pintype "bidirectional"))
    )
    (net (code "62") (name "Net-(IC7C-P$2)") (class "Default")
      (node (ref "IC7") (pin "16") (pinfunction "P$2_16") (pintype "output"))
      (node (ref "R5") (pin "P$5") (pinfunction "P$5_P$5") (pintype "bidirectional"))
    )
    (net (code "63") (name "Net-(IC7D-P$2)") (class "Default")
      (node (ref "IC7") (pin "15") (pinfunction "P$2_15") (pintype "output"))
      (node (ref "R5") (pin "P$7") (pinfunction "P$7_P$7") (pintype "bidirectional"))
    )
    (net (code "64") (name "Net-(IC7E-P$2)") (class "Default")
      (node (ref "IC7") (pin "14") (pinfunction "P$2_14") (pintype "output"))
      (node (ref "R6") (pin "P$1") (pinfunction "P$1_P$1") (pintype "bidirectional"))
    )
    (net (code "65") (name "Net-(IC7F-P$2)") (class "Default")
      (node (ref "IC7") (pin "13") (pinfunction "P$2_13") (pintype "output"))
      (node (ref "R6") (pin "P$3") (pinfunction "P$3_P$3") (pintype "bidirectional"))
    )
    (net (code "66") (name "Net-(IC7G-P$2)") (class "Default")
      (node (ref "IC7") (pin "12") (pinfunction "P$2_12") (pintype "output"))
      (node (ref "R6") (pin "P$5") (pinfunction "P$5_P$5") (pintype "bidirectional"))
    )
    (net (code "67") (name "Net-(IC7I-P$2)") (class "Default")
      (node (ref "IC7") (pin "11") (pinfunction "P$2_11") (pintype "output"))
      (node (ref "R6") (pin "P$7") (pinfunction "P$7_P$7") (pintype "bidirectional"))
    )
    (net (code "68") (name "Net-(INT_CLK-Pad1)") (class "Default")
      (node (ref "INT_CLK") (pin "1") (pinfunction "1_1") (pintype "passive"))
      (node (ref "R47") (pin "1") (pinfunction "1_1") (pintype "passive"))
    )
    (net (code "69") (name "Net-(LEDS1-Pad1)") (class "Default")
      (node (ref "LEDS1") (pin "1") (pinfunction "1_1") (pintype "passive"))
      (node (ref "R3") (pin "P$2") (pinfunction "P$2_P$2") (pintype "bidirectional"))
    )
    (net (code "70") (name "Net-(LEDS1-Pad2)") (class "Default")
      (node (ref "LEDS1") (pin "2") (pinfunction "2_2") (pintype "passive"))
      (node (ref "R3") (pin "P$4") (pinfunction "P$4_P$4") (pintype "bidirectional"))
    )
    (net (code "71") (name "Net-(LEDS1-Pad3)") (class "Default")
      (node (ref "LEDS1") (pin "3") (pinfunction "3_3") (pintype "passive"))
      (node (ref "R3") (pin "P$6") (pinfunction "P$6_P$6") (pintype "bidirectional"))
    )
    (net (code "72") (name "Net-(LEDS1-Pad4)") (class "Default")
      (node (ref "LEDS1") (pin "4") (pinfunction "4_4") (pintype "passive"))
      (node (ref "R3") (pin "P$8") (pinfunction "P$8_P$8") (pintype "bidirectional"))
    )
    (net (code "73") (name "Net-(LEDS1-Pad5)") (class "Default")
      (node (ref "LEDS1") (pin "5") (pinfunction "5_5") (pintype "passive"))
      (node (ref "R4") (pin "P$2") (pinfunction "P$2_P$2") (pintype "bidirectional"))
    )
    (net (code "74") (name "Net-(LEDS1-Pad6)") (class "Default")
      (node (ref "LEDS1") (pin "6") (pinfunction "6_6") (pintype "passive"))
      (node (ref "R4") (pin "P$4") (pinfunction "P$4_P$4") (pintype "bidirectional"))
    )
    (net (code "75") (name "Net-(LEDS1-Pad7)") (class "Default")
      (node (ref "LEDS1") (pin "7") (pinfunction "7_7") (pintype "passive"))
      (node (ref "R4") (pin "P$6") (pinfunction "P$6_P$6") (pintype "bidirectional"))
    )
    (net (code "76") (name "Net-(LEDS1-Pad8)") (class "Default")
      (node (ref "LEDS1") (pin "8") (pinfunction "8_8") (pintype "passive"))
      (node (ref "R4") (pin "P$8") (pinfunction "P$8_P$8") (pintype "bidirectional"))
    )
    (net (code "77") (name "Net-(LEDS2-Pad1)") (class "Default")
      (node (ref "LEDS2") (pin "1") (pinfunction "1_1") (pintype "passive"))
      (node (ref "R5") (pin "P$2") (pinfunction "P$2_P$2") (pintype "bidirectional"))
    )
    (net (code "78") (name "Net-(LEDS2-Pad2)") (class "Default")
      (node (ref "LEDS2") (pin "2") (pinfunction "2_2") (pintype "passive"))
      (node (ref "R5") (pin "P$4") (pinfunction "P$4_P$4") (pintype "bidirectional"))
    )
    (net (code "79") (name "Net-(LEDS2-Pad3)") (class "Default")
      (node (ref "LEDS2") (pin "3") (pinfunction "3_3") (pintype "passive"))
      (node (ref "R5") (pin "P$6") (pinfunction "P$6_P$6") (pintype "bidirectional"))
    )
    (net (code "80") (name "Net-(LEDS2-Pad4)") (class "Default")
      (node (ref "LEDS2") (pin "4") (pinfunction "4_4") (pintype "passive"))
      (node (ref "R5") (pin "P$8") (pinfunction "P$8_P$8") (pintype "bidirectional"))
    )
    (net (code "81") (name "Net-(LEDS2-Pad5)") (class "Default")
      (node (ref "LEDS2") (pin "5") (pinfunction "5_5") (pintype "passive"))
      (node (ref "R6") (pin "P$2") (pinfunction "P$2_P$2") (pintype "bidirectional"))
    )
    (net (code "82") (name "Net-(LEDS2-Pad6)") (class "Default")
      (node (ref "LEDS2") (pin "6") (pinfunction "6_6") (pintype "passive"))
      (node (ref "R6") (pin "P$4") (pinfunction "P$4_P$4") (pintype "bidirectional"))
    )
    (net (code "83") (name "Net-(LEDS2-Pad7)") (class "Default")
      (node (ref "LEDS2") (pin "7") (pinfunction "7_7") (pintype "passive"))
      (node (ref "R6") (pin "P$6") (pinfunction "P$6_P$6") (pintype "bidirectional"))
    )
    (net (code "84") (name "Net-(LEDS2-Pad8)") (class "Default")
      (node (ref "LEDS2") (pin "8") (pinfunction "8_8") (pintype "passive"))
      (node (ref "R6") (pin "P$8") (pinfunction "P$8_P$8") (pintype "bidirectional"))
    )
    (net (code "85") (name "Net-(POTR-Pad1)") (class "Default")
      (node (ref "POTR") (pin "1") (pinfunction "1_1") (pintype "passive"))
      (node (ref "R7") (pin "P$1") (pinfunction "P$1_P$1") (pintype "bidirectional"))
    )
    (net (code "86") (name "Net-(POTR-Pad2)") (class "Default")
      (node (ref "POTR") (pin "2") (pinfunction "2_2") (pintype "passive"))
      (node (ref "R7") (pin "P$3") (pinfunction "P$3_P$3") (pintype "bidirectional"))
    )
    (net (code "87") (name "Net-(POTR-Pad3)") (class "Default")
      (node (ref "POTR") (pin "3") (pinfunction "3_3") (pintype "passive"))
      (node (ref "R7") (pin "P$5") (pinfunction "P$5_P$5") (pintype "bidirectional"))
    )
    (net (code "88") (name "Net-(POTR-Pad4)") (class "Default")
      (node (ref "POTR") (pin "4") (pinfunction "4_4") (pintype "passive"))
      (node (ref "R7") (pin "P$7") (pinfunction "P$7_P$7") (pintype "bidirectional"))
    )
    (net (code "89") (name "Net-(POTR-Pad5)") (class "Default")
      (node (ref "POTR") (pin "5") (pinfunction "5_5") (pintype "passive"))
      (node (ref "R8") (pin "P$1") (pinfunction "P$1_P$1") (pintype "bidirectional"))
    )
    (net (code "90") (name "Net-(POTR-Pad6)") (class "Default")
      (node (ref "POTR") (pin "6") (pinfunction "6_6") (pintype "passive"))
      (node (ref "R8") (pin "P$3") (pinfunction "P$3_P$3") (pintype "bidirectional"))
    )
    (net (code "91") (name "Net-(POTR-Pad7)") (class "Default")
      (node (ref "POTR") (pin "7") (pinfunction "7_7") (pintype "passive"))
      (node (ref "R8") (pin "P$5") (pinfunction "P$5_P$5") (pintype "bidirectional"))
    )
    (net (code "92") (name "Net-(POTR-Pad8)") (class "Default")
      (node (ref "POTR") (pin "8") (pinfunction "8_8") (pintype "passive"))
      (node (ref "R8") (pin "P$7") (pinfunction "P$7_P$7") (pintype "bidirectional"))
    )
    (net (code "93") (name "Net-(POTR-Pad9)") (class "Default")
      (node (ref "POTR") (pin "9") (pinfunction "9_9") (pintype "passive"))
      (node (ref "R9") (pin "P$1") (pinfunction "P$1_P$1") (pintype "bidirectional"))
    )
    (net (code "94") (name "Net-(POTR-Pad10)") (class "Default")
      (node (ref "POTR") (pin "10") (pinfunction "10_10") (pintype "passive"))
      (node (ref "R9") (pin "P$3") (pinfunction "P$3_P$3") (pintype "bidirectional"))
    )
    (net (code "95") (name "Net-(POTR-Pad11)") (class "Default")
      (node (ref "POTR") (pin "11") (pinfunction "11_11") (pintype "passive"))
      (node (ref "R9") (pin "P$5") (pinfunction "P$5_P$5") (pintype "bidirectional"))
    )
    (net (code "96") (name "Net-(POTR-Pad12)") (class "Default")
      (node (ref "POTR") (pin "12") (pinfunction "12_12") (pintype "passive"))
      (node (ref "R9") (pin "P$7") (pinfunction "P$7_P$7") (pintype "bidirectional"))
    )
    (net (code "97") (name "Net-(POTR-Pad13)") (class "Default")
      (node (ref "POTR") (pin "13") (pinfunction "13_13") (pintype "passive"))
      (node (ref "R10") (pin "P$1") (pinfunction "P$1_P$1") (pintype "bidirectional"))
    )
    (net (code "98") (name "Net-(POTR-Pad14)") (class "Default")
      (node (ref "POTR") (pin "14") (pinfunction "14_14") (pintype "passive"))
      (node (ref "R10") (pin "P$3") (pinfunction "P$3_P$3") (pintype "bidirectional"))
    )
    (net (code "99") (name "Net-(POTR-Pad15)") (class "Default")
      (node (ref "POTR") (pin "15") (pinfunction "15_15") (pintype "passive"))
      (node (ref "R10") (pin "P$5") (pinfunction "P$5_P$5") (pintype "bidirectional"))
    )
    (net (code "100") (name "Net-(POTR-Pad16)") (class "Default")
      (node (ref "POTR") (pin "16") (pinfunction "16_16") (pintype "passive"))
      (node (ref "R10") (pin "P$7") (pinfunction "P$7_P$7") (pintype "bidirectional"))
    )
    (net (code "101") (name "Net-(R38-Pad2)") (class "Default")
      (node (ref "R38") (pin "2") (pinfunction "2_2") (pintype "passive"))
      (node (ref "SEQ_VOLT") (pin "1") (pinfunction "1_1") (pintype "passive"))
    )
    (net (code "102") (name "Net-(R43-Pad2)") (class "Default")
      (node (ref "R43") (pin "2") (pinfunction "2_2") (pintype "passive"))
      (node (ref "R44") (pin "2") (pinfunction "2_2") (pintype "passive"))
      (node (ref "R45") (pin "1") (pinfunction "1_1") (pintype "passive"))
    )
    (net (code "103") (name "RESET") (class "Default")
      (node (ref "IC1") (pin "10") (pinfunction "10_PB7_10") (pintype "bidirectional"))
      (node (ref "ICSP1") (pin "5") (pinfunction "3RST_5") (pintype "bidirectional"))
    )
    (net (code "104") (name "SCK") (class "Default")
      (node (ref "IC1") (pin "3") (pinfunction "3_PB2_3") (pintype "bidirectional"))
      (node (ref "ICSP1") (pin "3") (pinfunction "2SCK_3") (pintype "bidirectional"))
      (node (ref "R40") (pin "2") (pinfunction "2_2") (pintype "passive"))
    )
  )
)
